# Controller_Yanuar.net
KiCad netlist of a schematic drawn in EAGLE
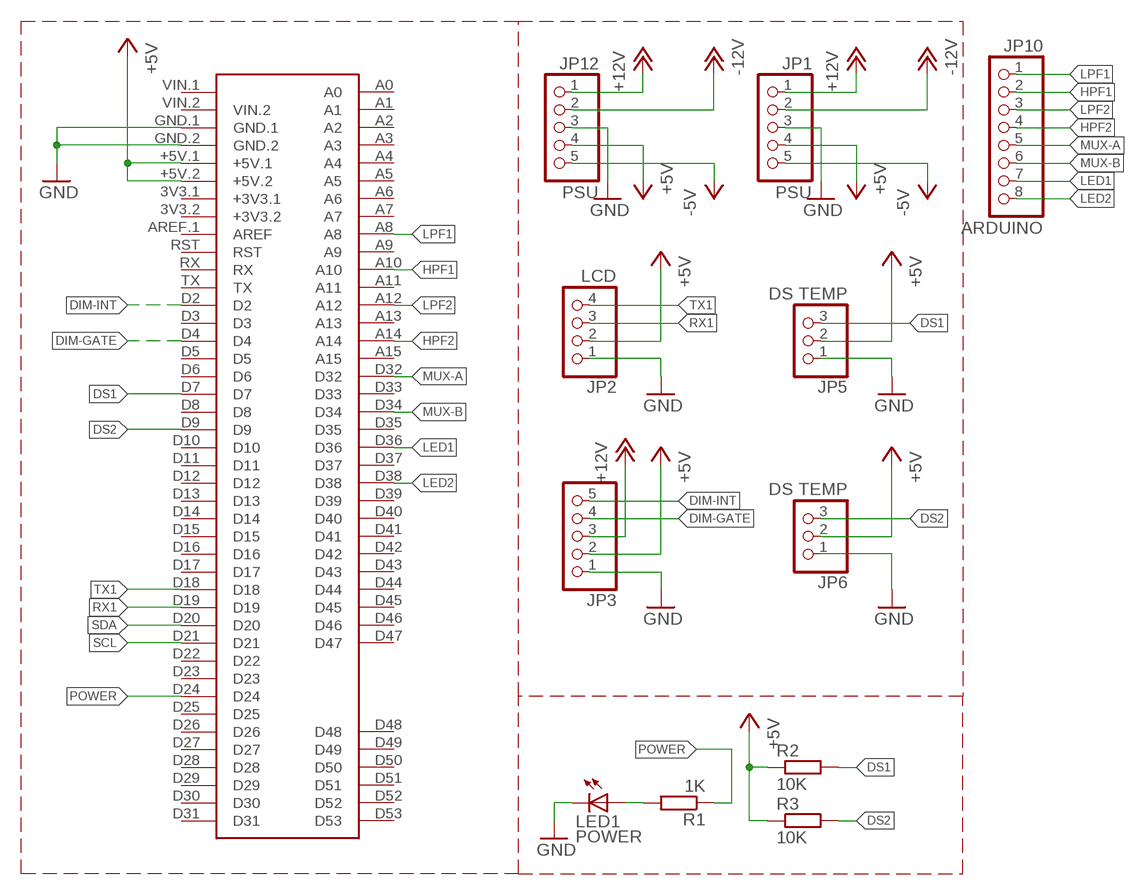
[diagram p0: schematic, sheet 1]

(export (version "E")
  (design (tool "Eeschema 10.0.6"))
  (components
    (comp (ref "JP1")
      (value "PSU")
      (footprint "eagle-import:1X05")
      (libsource (lib "eagle-import") (part "PINHD-1X5{dblquote}"))
    )
    (comp (ref "JP2")
      (value "LCD")
      (footprint "eagle-import:1X04")
      (libsource (lib "eagle-import") (part "PINHD-1X4"))
    )
    (comp (ref "JP3")
      (value "PINHD-1X5\"")
      (footprint "eagle-import:1X05")
      (libsource (lib "eagle-import") (part "PINHD-1X5{dblquote}"))
    )
    (comp (ref "JP5")
      (value "DS TEMP")
      (footprint "eagle-import:1X03")
      (libsource (lib "eagle-import") (part "PINHD-1X3"))
    )
    (comp (ref "JP6")
      (value "DS TEMP")
      (footprint "eagle-import:1X03")
      (libsource (lib "eagle-import") (part "PINHD-1X3"))
    )
    (comp (ref "JP10")
      (value "ARDUINO")
      (footprint "eagle-import:1X08")
      (libsource (lib "eagle-import") (part "PINHD-1X8"))
    )
    (comp (ref "JP12")
      (value "PSU")
      (footprint "eagle-import:1X05")
      (libsource (lib "eagle-import") (part "PINHD-1X5{dblquote}"))
    )
    (comp (ref "LED1")
      (value "POWER")
      (footprint "eagle-import:LED3MM")
      (libsource (lib "eagle-import") (part "LEDLED3MM"))
    )
    (comp (ref "R1")
      (value "1K")
      (footprint "eagle-import:0207_7")
      (libsource (lib "eagle-import") (part "R-EU_0207/7"))
    )
    (comp (ref "R2")
      (value "10K")
      (footprint "eagle-import:0207_15")
      (libsource (lib "eagle-import") (part "R-EU_0207/15"))
    )
    (comp (ref "R3")
      (value "10K")
      (footprint "eagle-import:0207_15")
      (libsource (lib "eagle-import") (part "R-EU_0207/15"))
    )
    (comp (ref "U$1")
      (value "MEGA2560_MIKRO")
      (footprint "eagle-import:MEGA2560_MIKRO")
      (libsource (lib "eagle-import") (part "MEGA2560_MIKRO"))
    )
  )
  (nets
    (net (code "1") (name "+5V") (class "Default")
      (node (ref "JP1") (pin "4") (pinfunction "4_4") (pintype "passive"))
      (node (ref "JP12") (pin "4") (pinfunction "4_4") (pintype "passive"))
      (node (ref "JP2") (pin "2") (pinfunction "2_2") (pintype "passive"))
      (node (ref "JP3") (pin "2") (pinfunction "2_2") (pintype "passive"))
      (node (ref "JP5") (pin "2") (pinfunction "2_2") (pintype "passive"))
      (node (ref "JP6") (pin "2") (pinfunction "2_2") (pintype "passive"))
      (node (ref "R2") (pin "1") (pinfunction "1_1") (pintype "passive"))
      (node (ref "R3") (pin "1") (pinfunction "1_1") (pintype "passive"))
      (node (ref "U$1") (pin "+5V.1") (pinfunction "+5V.1_+5V.1") (pintype "bidirectional"))
      (node (ref "U$1") (pin "+5V.2") (pinfunction "+5V.2_+5V.2") (pintype "bidirectional"))
    )
    (net (code "2") (name "+12V") (class "Default")
      (node (ref "JP1") (pin "1") (pinfunction "1_1") (pintype "passive"))
      (node (ref "JP12") (pin "1") (pinfunction "1_1") (pintype "passive"))
      (node (ref "JP3") (pin "3") (pinfunction "3_3") (pintype "passive"))
    )
    (net (code "3") (name "-5V") (class "Default")
      (node (ref "JP1") (pin "5") (pinfunction "5_5") (pintype "passive"))
      (node (ref "JP12") (pin "5") (pinfunction "5_5") (pintype "passive"))
    )
    (net (code "4") (name "-12V") (class "Default")
      (node (ref "JP1") (pin "2") (pinfunction "2_2") (pintype "passive"))
      (node (ref "JP12") (pin "2") (pinfunction "2_2") (pintype "passive"))
    )
    (net (code "5") (name "DIM-GATE") (class "Default")
      (node (ref "JP3") (pin "4") (pinfunction "4_4") (pintype "passive"))
      (node (ref "U$1") (pin "D4") (pinfunction "D4_D4") (pintype "bidirectional"))
    )
    (net (code "6") (name "DIM-INT") (class "Default")
      (node (ref "JP3") (pin "5") (pinfunction "5_5") (pintype "passive"))
      (node (ref "U$1") (pin "D2") (pinfunction "D2_D2") (pintype "bidirectional"))
    )
    (net (code "7") (name "DS1") (class "Default")
      (node (ref "JP5") (pin "3") (pinfunction "3_3") (pintype "passive"))
      (node (ref "R2") (pin "2") (pinfunction "2_2") (pintype "passive"))
      (node (ref "U$1") (pin "D7") (pinfunction "D7_D7") (pintype "bidirectional"))
    )
    (net (code "8") (name "DS2") (class "Default")
      (node (ref "JP6") (pin "3") (pinfunction "3_3") (pintype "passive"))
      (node (ref "R3") (pin "2") (pinfunction "2_2") (pintype "passive"))
      (node (ref "U$1") (pin "D9") (pinfunction "D9_D9") (pintype "bidirectional"))
    )
    (net (code "9") (name "GND") (class "Default")
      (node (ref "JP1") (pin "3") (pinfunction "3_3") (pintype "passive"))
      (node (ref "JP12") (pin "3") (pinfunction "3_3") (pintype "passive"))
      (node (ref "JP2") (pin "1") (pinfunction "1_1") (pintype "passive"))
      (node (ref "JP3") (pin "1") (pinfunction "1_1") (pintype "passive"))
      (node (ref "JP5") (pin "1") (pinfunction "1_1") (pintype "passive"))
      (node (ref "JP6") (pin "1") (pinfunction "1_1") (pintype "passive"))
      (node (ref "LED1") (pin "K") (pinfunction "C_K") (pintype "passive"))
      (node (ref "U$1") (pin "GND.1") (pinfunction "GND.1_GND.1") (pintype "bidirectional"))
      (node (ref "U$1") (pin "GND.2") (pinfunction "GND.2_GND.2") (pintype "bidirectional"))
    )
    (net (code "10") (name "HPF1") (class "Default")
      (node (ref "JP10") (pin "2") (pinfunction "2_2") (pintype "passive"))
      (node (ref "U$1") (pin "A10") (pinfunction "A10_A10") (pintype "bidirectional"))
    )
    (net (code "11") (name "HPF2") (class "Default")
      (node (ref "JP10") (pin "4") (pinfunction "4_4") (pintype "passive"))
      (node (ref "U$1") (pin "A14") (pinfunction "A14_A14") (pintype "bidirectional"))
    )
    (net (code "12") (name "LED1") (class "Default")
      (node (ref "JP10") (pin "7") (pinfunction "7_7") (pintype "passive"))
      (node (ref "U$1") (pin "D36") (pinfunction "D36_D36") (pintype "bidirectional"))
    )
    (net (code "13") (name "LED2") (class "Default")
      (node (ref "JP10") (pin "8") (pinfunction "8_8") (pintype "passive"))
      (node (ref "U$1") (pin "D38") (pinfunction "D38_D38") (pintype "bidirectional"))
    )
    (net (code "14") (name "LPF1") (class "Default")
      (node (ref "JP10") (pin "1") (pinfunction "1_1") (pintype "passive"))
      (node (ref "U$1") (pin "A8") (pinfunction "A8_A8") (pintype "bidirectional"))
    )
    (net (code "15") (name "LPF2") (class "Default")
      (node (ref "JP10") (pin "3") (pinfunction "3_3") (pintype "passive"))
      (node (ref "U$1") (pin "A12") (pinfunction "A12_A12") (pintype "bidirectional"))
    )
    (net (code "16") (name "MUX-A") (class "Default")
      (node (ref "JP10") (pin "5") (pinfunction "5_5") (pintype "passive"))
      (node (ref "U$1") (pin "D32") (pinfunction "D32_D32") (pintype "bidirectional"))
    )
    (net (code "17") (name "MUX-B") (class "Default")
      (node (ref "JP10") (pin "6") (pinfunction "6_6") (pintype "passive"))
      (node (ref "U$1") (pin "D34") (pinfunction "D34_D34") (pintype "bidirectional"))
    )
    (net (code "18") (name "Net-(LED1-PadA)") (class "Default")
      (node (ref "LED1") (pin "A") (pinfunction "A_A") (pintype "passive"))
      (node (ref "R1") (pin "2") (pinfunction "2_2") (pintype "passive"))
    )
    (net (code "19") (name "POWER") (class "Default")
      (node (ref "R1") (pin "1") (pinfunction "1_1") (pintype "passive"))
      (node (ref "U$1") (pin "D24") (pinfunction "D24_D24") (pintype "bidirectional"))
    )
    (net (code "20") (name "RX1") (class "Default")
      (node (ref "JP2") (pin "3") (pinfunction "3_3") (pintype "passive"))
      (node (ref "U$1") (pin "D19") (pinfunction "D19_D19") (pintype "bidirectional"))
    )
    (net (code "21") (name "SCL") (class "Default")
      (node (ref "U$1") (pin "D21") (pinfunction "D21_D21") (pintype "bidirectional"))
    )
    (net (code "22") (name "SDA") (class "Default")
      (node (ref "U$1") (pin "D20") (pinfunction "D20_D20") (pintype "bidirectional"))
    )
    (net (code "23") (name "TX1") (class "Default")
      (node (ref "JP2") (pin "4") (pinfunction "4_4") (pintype "passive"))
      (node (ref "U$1") (pin "D18") (pinfunction "D18_D18") (pintype "bidirectional"))
    )
    (net (code "24") (name "unconnected-(U$1-+3V3.1-Pad3V3.1)") (class "Default")
      (node (ref "U$1") (pin "3V3.1") (pinfunction "+3V3.1_3V3.1") (pintype "bidirectional"))
    )
    (net (code "25") (name "unconnected-(U$1-+3V3.2-Pad3V3.2)") (class "Default")
      (node (ref "U$1") (pin "3V3.2") (pinfunction "+3V3.2_3V3.2") (pintype "bidirectional"))
    )
    (net (code "26") (name "unconnected-(U$1-AREF-PadAREF.1)") (class "Default")
      (node (ref "U$1") (pin "AREF.1") (pinfunction "AREF_AREF.1") (pintype "bidirectional"))
    )
    (net (code "27") (name "unconnected-(U$1-PadA0)") (class "Default")
      (node (ref "U$1") (pin "A0") (pinfunction "A0_A0") (pintype "bidirectional"))
    )
    (net (code "28") (name "unconnected-(U$1-PadA1)") (class "Default")
      (node (ref "U$1") (pin "A1") (pinfunction "A1_A1") (pintype "bidirectional"))
    )
    (net (code "29") (name "unconnected-(U$1-PadA2)") (class "Default")
      (node (ref "U$1") (pin "A2") (pinfunction "A2_A2") (pintype "bidirectional"))
    )
    (net (code "30") (name "unconnected-(U$1-PadA3)") (class "Default")
      (node (ref "U$1") (pin "A3") (pinfunction "A3_A3") (pintype "bidirectional"))
    )
    (net (code "31") (name "unconnected-(U$1-PadA4)") (class "Default")
      (node (ref "U$1") (pin "A4") (pinfunction "A4_A4") (pintype "bidirectional"))
    )
    (net (code "32") (name "unconnected-(U$1-PadA5)") (class "Default")
      (node (ref "U$1") (pin "A5") (pinfunction "A5_A5") (pintype "bidirectional"))
    )
    (net (code "33") (name "unconnected-(U$1-PadA6)") (class "Default")
      (node (ref "U$1") (pin "A6") (pinfunction "A6_A6") (pintype "bidirectional"))
    )
    (net (code "34") (name "unconnected-(U$1-PadA7)") (class "Default")
      (node (ref "U$1") (pin "A7") (pinfunction "A7_A7") (pintype "bidirectional"))
    )
    (net (code "35") (name "unconnected-(U$1-PadA9)") (class "Default")
      (node (ref "U$1") (pin "A9") (pinfunction "A9_A9") (pintype "bidirectional"))
    )
    (net (code "36") (name "unconnected-(U$1-PadA11)") (class "Default")
      (node (ref "U$1") (pin "A11") (pinfunction "A11_A11") (pintype "bidirectional"))
    )
    (net (code "37") (name "unconnected-(U$1-PadA13)") (class "Default")
      (node (ref "U$1") (pin "A13") (pinfunction "A13_A13") (pintype "bidirectional"))
    )
    (net (code "38") (name "unconnected-(U$1-PadA15)") (class "Default")
      (node (ref "U$1") (pin "A15") (pinfunction "A15_A15") (pintype "bidirectional"))
    )
    (net (code "39") (name "unconnected-(U$1-PadD3)") (class "Default")
      (node (ref "U$1") (pin "D3") (pinfunction "D3_D3") (pintype "bidirectional"))
    )
    (net (code "40") (name "unconnected-(U$1-PadD5)") (class "Default")
      (node (ref "U$1") (pin "D5") (pinfunction "D5_D5") (pintype "bidirectional"))
    )
    (net (code "41") (name "unconnected-(U$1-PadD6)") (class "Default")
      (node (ref "U$1") (pin "D6") (pinfunction "D6_D6") (pintype "bidirectional"))
    )
    (net (code "42") (name "unconnected-(U$1-PadD8)") (class "Default")
      (node (ref "U$1") (pin "D8") (pinfunction "D8_D8") (pintype "bidirectional"))
    )
    (net (code "43") (name "unconnected-(U$1-PadD10)") (class "Default")
      (node (ref "U$1") (pin "D10") (pinfunction "D10_D10") (pintype "bidirectional"))
    )
    (net (code "44") (name "unconnected-(U$1-PadD11)") (class "Default")
      (node (ref "U$1") (pin "D11") (pinfunction "D11_D11") (pintype "bidirectional"))
    )
    (net (code "45") (name "unconnected-(U$1-PadD12)") (class "Default")
      (node (ref "U$1") (pin "D12") (pinfunction "D12_D12") (pintype "bidirectional"))
    )
    (net (code "46") (name "unconnected-(U$1-PadD13)") (class "Default")
      (node (ref "U$1") (pin "D13") (pinfunction "D13_D13") (pintype "bidirectional"))
    )
    (net (code "47") (name "unconnected-(U$1-PadD14)") (class "Default")
      (node (ref "U$1") (pin "D14") (pinfunction "D14_D14") (pintype "bidirectional"))
    )
    (net (code "48") (name "unconnected-(U$1-PadD15)") (class "Default")
      (node (ref "U$1") (pin "D15") (pinfunction "D15_D15") (pintype "bidirectional"))
    )
    (net (code "49") (name "unconnected-(U$1-PadD16)") (class "Default")
      (node (ref "U$1") (pin "D16") (pinfunction "D16_D16") (pintype "bidirectional"))
    )
    (net (code "50") (name "unconnected-(U$1-PadD17)") (class "Default")
      (node (ref "U$1") (pin "D17") (pinfunction "D17_D17") (pintype "bidirectional"))
    )
    (net (code "51") (name "unconnected-(U$1-PadD22)") (class "Default")
      (node (ref "U$1") (pin "D22") (pinfunction "D22_D22") (pintype "bidirectional"))
    )
    (net (code "52") (name "unconnected-(U$1-PadD23)") (class "Default")
      (node (ref "U$1") (pin "D23") (pinfunction "D23_D23") (pintype "bidirectional"))
    )
    (net (code "53") (name "unconnected-(U$1-PadD25)") (class "Default")
      (node (ref "U$1") (pin "D25") (pinfunction "D25_D25") (pintype "bidirectional"))
    )
    (net (code "54") (name "unconnected-(U$1-PadD26)") (class "Default")
      (node (ref "U$1") (pin "D26") (pinfunction "D26_D26") (pintype "bidirectional"))
    )
    (net (code "55") (name "unconnected-(U$1-PadD27)") (class "Default")
      (node (ref "U$1") (pin "D27") (pinfunction "D27_D27") (pintype "bidirectional"))
    )
    (net (code "56") (name "unconnected-(U$1-PadD28)") (class "Default")
      (node (ref "U$1") (pin "D28") (pinfunction "D28_D28") (pintype "bidirectional"))
    )
    (net (code "57") (name "unconnected-(U$1-PadD29)") (class "Default")
      (node (ref "U$1") (pin "D29") (pinfunction "D29_D29") (pintype "bidirectional"))
    )
    (net (code "58") (name "unconnected-(U$1-PadD30)") (class "Default")
      (node (ref "U$1") (pin "D30") (pinfunction "D30_D30") (pintype "bidirectional"))
    )
    (net (code "59") (name "unconnected-(U$1-PadD31)") (class "Default")
      (node (ref "U$1") (pin "D31") (pinfunction "D31_D31") (pintype "bidirectional"))
    )
    (net (code "60") (name "unconnected-(U$1-PadD33)") (class "Default")
      (node (ref "U$1") (pin "D33") (pinfunction "D33_D33") (pintype "bidirectional"))
    )
    (net (code "61") (name "unconnected-(U$1-PadD35)") (class "Default")
      (node (ref "U$1") (pin "D35") (pinfunction "D35_D35") (pintype "bidirectional"))
    )
    (net (code "62") (name "unconnected-(U$1-PadD37)") (class "Default")
      (node (ref "U$1") (pin "D37") (pinfunction "D37_D37") (pintype "bidirectional"))
    )
    (net (code "63") (name "unconnected-(U$1-PadD39)") (class "Default")
      (node (ref "U$1") (pin "D39") (pinfunction "D39_D39") (pintype "bidirectional"))
    )
    (net (code "64") (name "unconnected-(U$1-PadD40)") (class "Default")
      (node (ref "U$1") (pin "D40") (pinfunction "D40_D40") (pintype "bidirectional"))
    )
    (net (code "65") (name "unconnected-(U$1-PadD41)") (class "Default")
      (node (ref "U$1") (pin "D41") (pinfunction "D41_D41") (pintype "bidirectional"))
    )
    (net (code "66") (name "unconnected-(U$1-PadD42)") (class "Default")
      (node (ref "U$1") (pin "D42") (pinfunction "D42_D42") (pintype "bidirectional"))
    )
    (net (code "67") (name "unconnected-(U$1-PadD43)") (class "Default")
      (node (ref "U$1") (pin "D43") (pinfunction "D43_D43") (pintype "bidirectional"))
    )
    (net (code "68") (name "unconnected-(U$1-PadD44)") (class "Default")
      (node (ref "U$1") (pin "D44") (pinfunction "D44_D44") (pintype "bidirectional"))
    )
    (net (code "69") (name "unconnected-(U$1-PadD45)") (class "Default")
      (node (ref "U$1") (pin "D45") (pinfunction "D45_D45") (pintype "bidirectional"))
    )
    (net (code "70") (name "unconnected-(U$1-PadD46)") (class "Default")
      (node (ref "U$1") (pin "D46") (pinfunction "D46_D46") (pintype "bidirectional"))
    )
    (net (code "71") (name "unconnected-(U$1-PadD47)") (class "Default")
      (node (ref "U$1") (pin "D47") (pinfunction "D47_D47") (pintype "bidirectional"))
    )
    (net (code "72") (name "unconnected-(U$1-PadD48)") (class "Default")
      (node (ref "U$1") (pin "D48") (pinfunction "D48_D48") (pintype "bidirectional"))
    )
    (net (code "73") (name "unconnected-(U$1-PadD49)") (class "Default")
      (node (ref "U$1") (pin "D49") (pinfunction "D49_D49") (pintype "bidirectional"))
    )
    (net (code "74") (name "unconnected-(U$1-PadD50)") (class "Default")
      (node (ref "U$1") (pin "D50") (pinfunction "D50_D50") (pintype "bidirectional"))
    )
    (net (code "75") (name "unconnected-(U$1-PadD51)") (class "Default")
      (node (ref "U$1") (pin "D51") (pinfunction "D51_D51") (pintype "bidirectional"))
    )
    (net (code "76") (name "unconnected-(U$1-PadD52)") (class "Default")
      (node (ref "U$1") (pin "D52") (pinfunction "D52_D52") (pintype "bidirectional"))
    )
    (net (code "77") (name "unconnected-(U$1-PadD53)") (class "Default")
      (node (ref "U$1") (pin "D53") (pinfunction "D53_D53") (pintype "bidirectional"))
    )
    (net (code "78") (name "unconnected-(U$1-PadRST)") (class "Default")
      (node (ref "U$1") (pin "RST") (pinfunction "RST_RST") (pintype "bidirectional"))
    )
    (net (code "79") (name "unconnected-(U$1-PadRX)") (class "Default")
      (node (ref "U$1") (pin "RX") (pinfunction "RX_RX") (pintype "bidirectional"))
    )
    (net (code "80") (name "unconnected-(U$1-PadTX)") (class "Default")
      (node (ref "U$1") (pin "TX") (pinfunction "TX_TX") (pintype "bidirectional"))
    )
    (net (code "81") (name "unconnected-(U$1-PadVIN.1)") (class "Default")
      (node (ref "U$1") (pin "VIN.1") (pinfunction "VIN.1_VIN.1") (pintype "bidirectional"))
    )
    (net (code "82") (name "unconnected-(U$1-PadVIN.2)") (class "Default")
      (node (ref "U$1") (pin "VIN.2") (pinfunction "VIN.2_VIN.2") (pintype "bidirectional"))
    )
  )
)
